# design.net
KiCad netlist of a schematic drawn in EasyEDA Pro
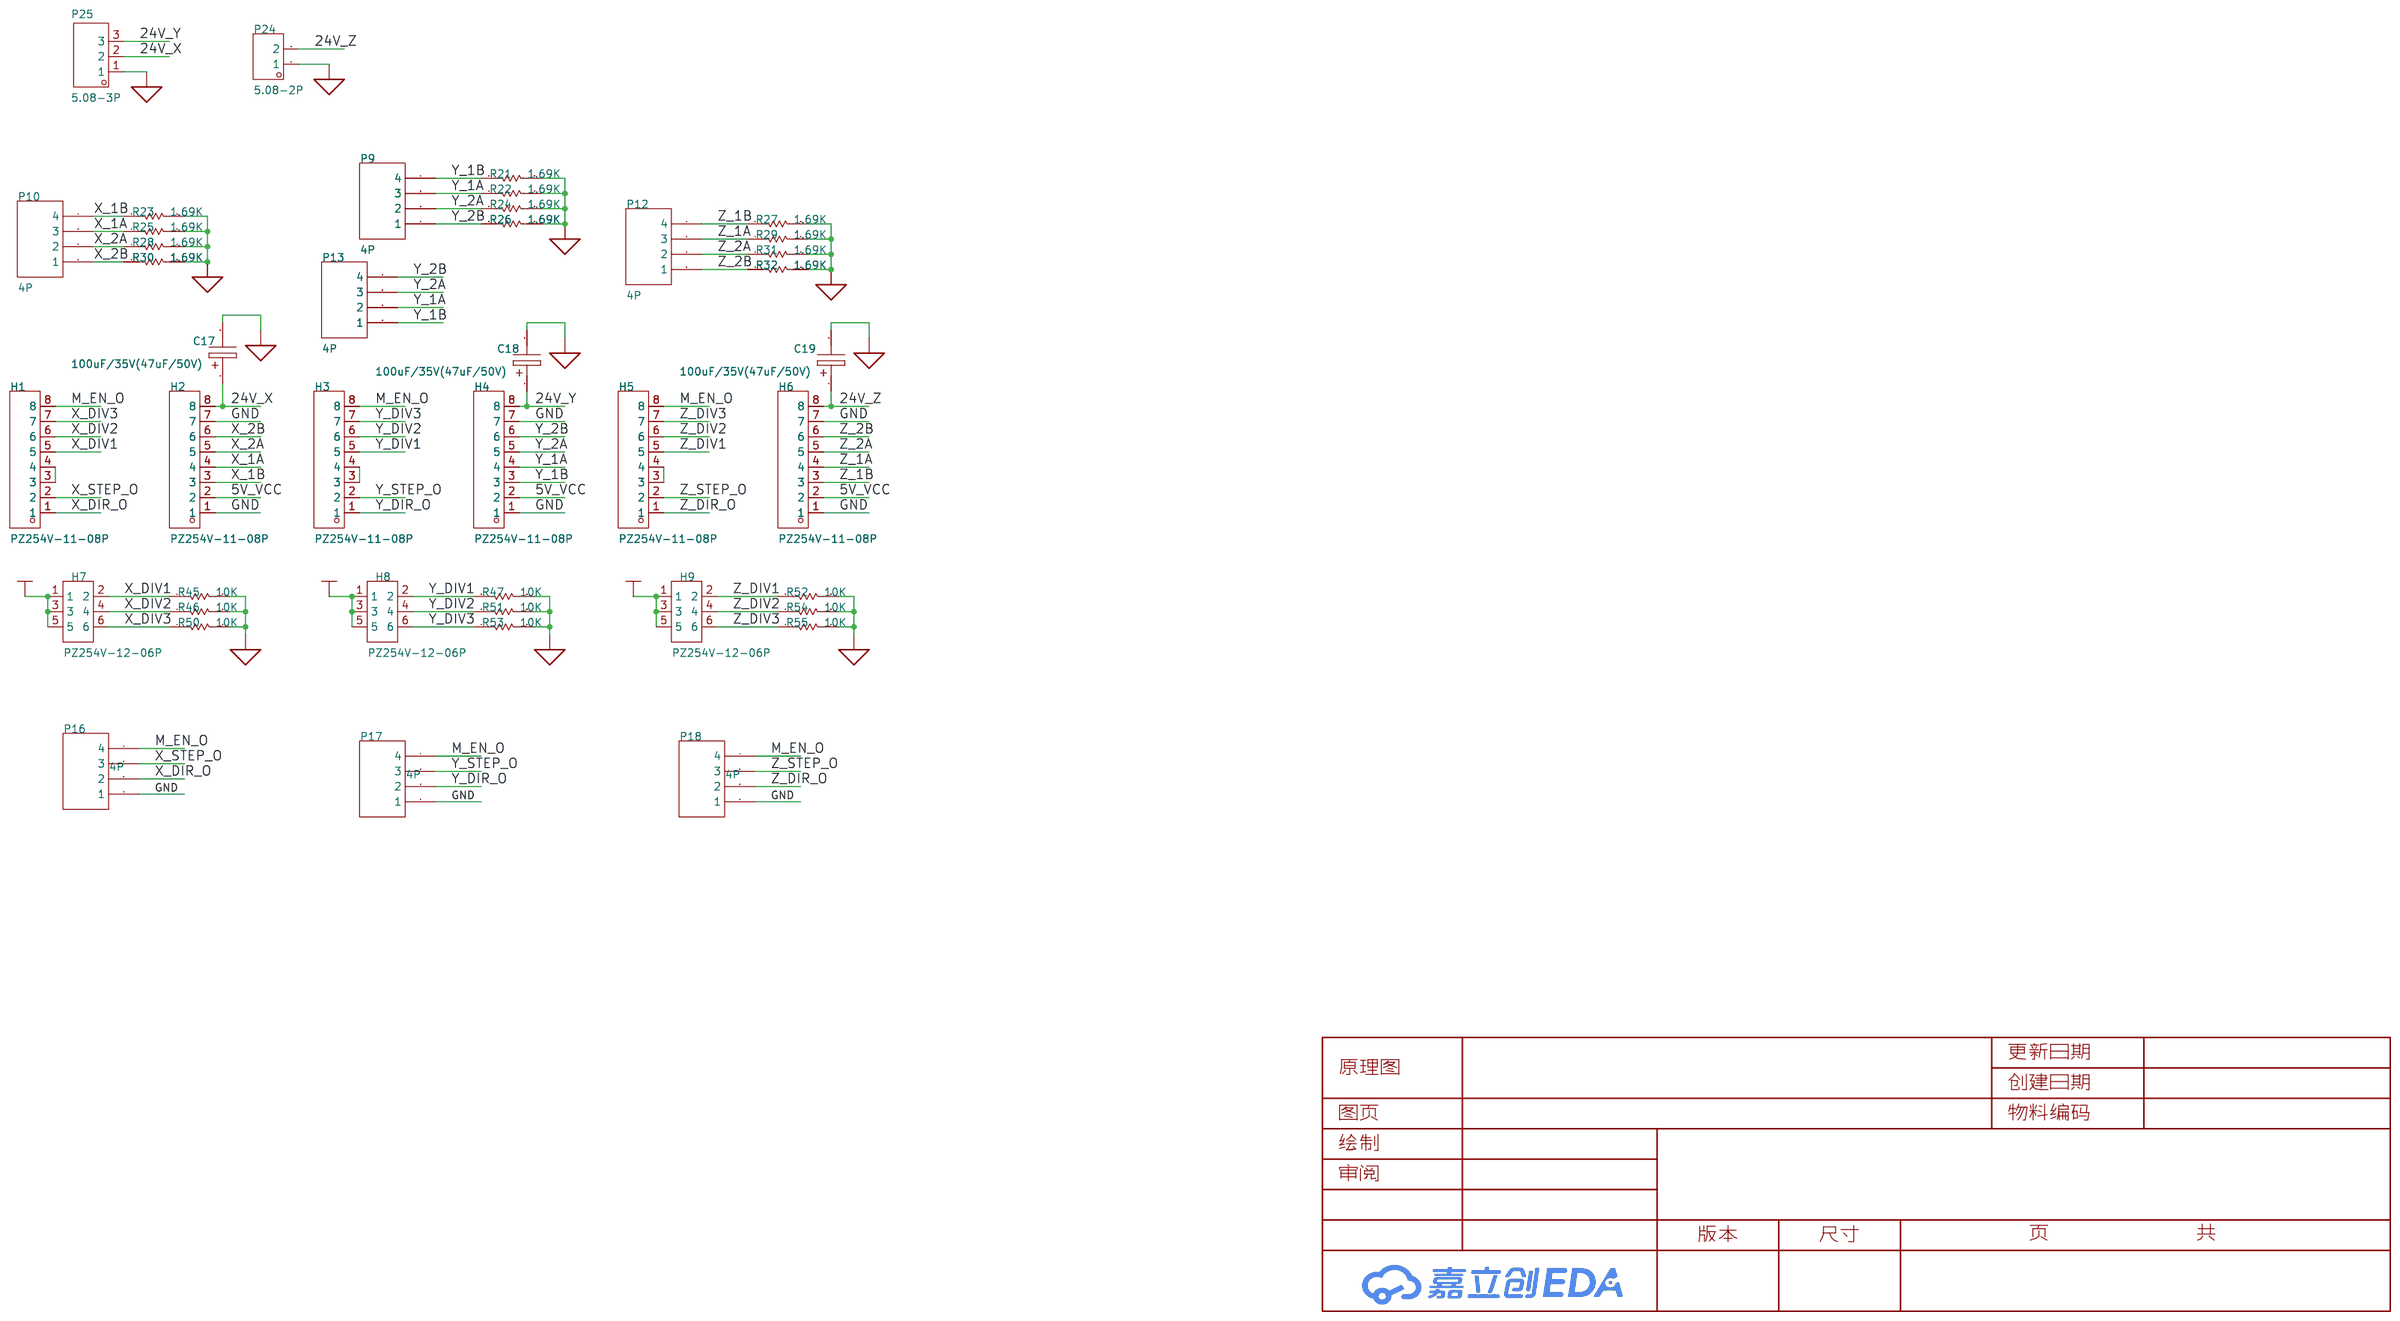
[diagram p0: schematic sheet]

(export (version "E")
  (design (tool "Eeschema 10.0.6"))
  (components
    (comp (ref "C17")
      (value "100uF/35V(47uF/50V)")
      (footprint "easyedapro:电解电容贴片10x10")
      (libsource (lib "easyedapro") (part "ELECTRO1"))
    )
    (comp (ref "C18")
      (value "100uF/35V(47uF/50V)")
      (footprint "easyedapro:电解电容贴片10x10")
      (libsource (lib "easyedapro") (part "ELECTRO1"))
    )
    (comp (ref "C19")
      (value "100uF/35V(47uF/50V)")
      (footprint "easyedapro:电解电容贴片10x10")
      (libsource (lib "easyedapro") (part "ELECTRO1"))
    )
    (comp (ref "H1")
      (value "PZ254V-11-08P")
      (footprint "easyedapro:HDR-TH_8P-P2.54-V-M")
      (fields (field (name "Manufacturer") "XFCN(兴飞)"))
      (libsource (lib "easyedapro") (part "PZ254V-11-08P"))
    )
    (comp (ref "H2")
      (value "PZ254V-11-08P")
      (footprint "easyedapro:HDR-TH_8P-P2.54-V-M")
      (fields (field (name "Manufacturer") "XFCN(兴飞)"))
      (libsource (lib "easyedapro") (part "PZ254V-11-08P"))
    )
    (comp (ref "H3")
      (value "PZ254V-11-08P")
      (footprint "easyedapro:HDR-TH_8P-P2.54-V-M")
      (fields (field (name "Manufacturer") "XFCN(兴飞)"))
      (libsource (lib "easyedapro") (part "PZ254V-11-08P"))
    )
    (comp (ref "H4")
      (value "PZ254V-11-08P")
      (footprint "easyedapro:HDR-TH_8P-P2.54-V-M")
      (fields (field (name "Manufacturer") "XFCN(兴飞)"))
      (libsource (lib "easyedapro") (part "PZ254V-11-08P"))
    )
    (comp (ref "H5")
      (value "PZ254V-11-08P")
      (footprint "easyedapro:HDR-TH_8P-P2.54-V-M")
      (fields (field (name "Manufacturer") "XFCN(兴飞)"))
      (libsource (lib "easyedapro") (part "PZ254V-11-08P"))
    )
    (comp (ref "H6")
      (value "PZ254V-11-08P")
      (footprint "easyedapro:HDR-TH_8P-P2.54-V-M")
      (fields (field (name "Manufacturer") "XFCN(兴飞)"))
      (libsource (lib "easyedapro") (part "PZ254V-11-08P"))
    )
    (comp (ref "H7")
      (value "PZ254V-12-06P")
      (footprint "easyedapro:HDR-TH_PZ254V-12-06P-A40")
      (description "排针2.54mm间距 直插 2x03位 直针外露4mm")
      (fields (field (name "Manufacturer") "XFCN(兴飞)"))
      (libsource (lib "easyedapro") (part "PZ254V-12-06P-A40"))
    )
    (comp (ref "H8")
      (value "PZ254V-12-06P")
      (footprint "easyedapro:HDR-TH_PZ254V-12-06P-A40")
      (description "排针2.54mm间距 直插 2x03位 直针外露4mm")
      (fields (field (name "Manufacturer") "XFCN(兴飞)"))
      (libsource (lib "easyedapro") (part "PZ254V-12-06P-A40"))
    )
    (comp (ref "H9")
      (value "PZ254V-12-06P")
      (footprint "easyedapro:HDR-TH_PZ254V-12-06P-A40")
      (description "排针2.54mm间距 直插 2x03位 直针外露4mm")
      (fields (field (name "Manufacturer") "XFCN(兴飞)"))
      (libsource (lib "easyedapro") (part "PZ254V-12-06P-A40"))
    )
    (comp (ref "P9")
      (value "4P")
      (footprint "easyedapro:HDR1X4_CON")
      (libsource (lib "easyedapro") (part "4P"))
    )
    (comp (ref "P10")
      (value "4P")
      (footprint "easyedapro:HDR1X4_CON")
      (libsource (lib "easyedapro") (part "4P"))
    )
    (comp (ref "P12")
      (value "4P")
      (footprint "easyedapro:HDR1X4_CON")
      (libsource (lib "easyedapro") (part "4P"))
    )
    (comp (ref "P13")
      (value "4P")
      (footprint "easyedapro:HDR1X4_CON")
      (libsource (lib "easyedapro") (part "4P"))
    )
    (comp (ref "P16") (value "4P") (libsource (lib "") (part "4P_1")))
    (comp (ref "P17") (value "4P") (libsource (lib "") (part "4P_1")))
    (comp (ref "P18") (value "4P") (libsource (lib "") (part "4P_1")))
    (comp (ref "P24")
      (value "5.08-2P")
      (footprint "easyedapro:CONN-TH_WJ2EDGVC-5.08-2P")
      (fields (field (name "Manufacturer") "KANGNEX(康奈克斯电气)"))
      (libsource (lib "easyedapro") (part "WJ2EDGVC-5.08-2P"))
    )
    (comp (ref "P25")
      (value "5.08-3P")
      (footprint "easyedapro:CONN-TH_3P-P5.08-WJ2EDGVC-3P")
      (description "连接器类型:板端/插座-闭口;间距:5.08mm;排数:1;每排PIN数:3;安装方式:直针;颜色:绿色;")
      (fields (field (name "Manufacturer") "KANGNEX(康奈克斯电气)"))
      (libsource (lib "easyedapro") (part "WJ2EDGVC-3P"))
    )
    (comp (ref "R21")
      (value "10K")
      (footprint "easyedapro:0603R")
      (description "Resistor")
      (libsource (lib "easyedapro") (part "10K"))
    )
    (comp (ref "R22")
      (value "10K")
      (footprint "easyedapro:0603R")
      (description "Resistor")
      (libsource (lib "easyedapro") (part "10K"))
    )
    (comp (ref "R23")
      (value "10K")
      (footprint "easyedapro:0603R")
      (description "Resistor")
      (libsource (lib "easyedapro") (part "10K"))
    )
    (comp (ref "R24")
      (value "10K")
      (footprint "easyedapro:0603R")
      (description "Resistor")
      (libsource (lib "easyedapro") (part "10K"))
    )
    (comp (ref "R25")
      (value "10K")
      (footprint "easyedapro:0603R")
      (description "Resistor")
      (libsource (lib "easyedapro") (part "10K"))
    )
    (comp (ref "R26")
      (value "10K")
      (footprint "easyedapro:0603R")
      (description "Resistor")
      (libsource (lib "easyedapro") (part "10K"))
    )
    (comp (ref "R27")
      (value "10K")
      (footprint "easyedapro:0603R")
      (description "Resistor")
      (libsource (lib "easyedapro") (part "10K"))
    )
    (comp (ref "R28")
      (value "10K")
      (footprint "easyedapro:0603R")
      (description "Resistor")
      (libsource (lib "easyedapro") (part "10K"))
    )
    (comp (ref "R29")
      (value "10K")
      (footprint "easyedapro:0603R")
      (description "Resistor")
      (libsource (lib "easyedapro") (part "10K"))
    )
    (comp (ref "R30")
      (value "10K")
      (footprint "easyedapro:0603R")
      (description "Resistor")
      (libsource (lib "easyedapro") (part "10K"))
    )
    (comp (ref "R31")
      (value "10K")
      (footprint "easyedapro:0603R")
      (description "Resistor")
      (libsource (lib "easyedapro") (part "10K"))
    )
    (comp (ref "R32")
      (value "10K")
      (footprint "easyedapro:0603R")
      (description "Resistor")
      (libsource (lib "easyedapro") (part "10K"))
    )
    (comp (ref "R45")
      (value "10K")
      (footprint "easyedapro:0603R")
      (description "Resistor")
      (libsource (lib "easyedapro") (part "10K"))
    )
    (comp (ref "R46")
      (value "10K")
      (footprint "easyedapro:0603R")
      (description "Resistor")
      (libsource (lib "easyedapro") (part "10K"))
    )
    (comp (ref "R47")
      (value "10K")
      (footprint "easyedapro:0603R")
      (description "Resistor")
      (libsource (lib "easyedapro") (part "10K"))
    )
    (comp (ref "R50")
      (value "10K")
      (footprint "easyedapro:0603R")
      (description "Resistor")
      (libsource (lib "easyedapro") (part "10K"))
    )
    (comp (ref "R51")
      (value "10K")
      (footprint "easyedapro:0603R")
      (description "Resistor")
      (libsource (lib "easyedapro") (part "10K"))
    )
    (comp (ref "R52")
      (value "10K")
      (footprint "easyedapro:0603R")
      (description "Resistor")
      (libsource (lib "easyedapro") (part "10K"))
    )
    (comp (ref "R53")
      (value "10K")
      (footprint "easyedapro:0603R")
      (description "Resistor")
      (libsource (lib "easyedapro") (part "10K"))
    )
    (comp (ref "R54")
      (value "10K")
      (footprint "easyedapro:0603R")
      (description "Resistor")
      (libsource (lib "easyedapro") (part "10K"))
    )
    (comp (ref "R55")
      (value "10K")
      (footprint "easyedapro:0603R")
      (description "Resistor")
      (libsource (lib "easyedapro") (part "10K"))
    )
  )
  (nets
    (net (code "1") (name "/24V_X") (class "Default")
      (node (ref "C17") (pin "1") (pintype "unspecified"))
      (node (ref "H2") (pin "8") (pinfunction "8_8") (pintype "unspecified"))
      (node (ref "P25") (pin "2") (pinfunction "2_2") (pintype "input"))
    )
    (net (code "2") (name "/24V_Y") (class "Default")
      (node (ref "C18") (pin "1") (pintype "unspecified"))
      (node (ref "H4") (pin "8") (pinfunction "8_8") (pintype "unspecified"))
      (node (ref "P25") (pin "3") (pinfunction "3_3") (pintype "input"))
    )
    (net (code "3") (name "/24V_Z") (class "Default")
      (node (ref "C19") (pin "1") (pintype "unspecified"))
      (node (ref "H6") (pin "8") (pinfunction "8_8") (pintype "unspecified"))
      (node (ref "P24") (pin "2") (pinfunction "2_2") (pintype "unspecified"))
    )
    (net (code "4") (name "/M_EN_O") (class "Default")
      (node (ref "H1") (pin "8") (pinfunction "8_8") (pintype "unspecified"))
      (node (ref "H3") (pin "8") (pinfunction "8_8") (pintype "unspecified"))
      (node (ref "H5") (pin "8") (pinfunction "8_8") (pintype "unspecified"))
      (node (ref "P16") (pin "4") (pinfunction "4_4") (pintype "input"))
      (node (ref "P17") (pin "4") (pinfunction "4_4") (pintype "input"))
      (node (ref "P18") (pin "4") (pinfunction "4_4") (pintype "input"))
    )
    (net (code "5") (name "/X_1A") (class "Default")
      (node (ref "H2") (pin "4") (pinfunction "4_4") (pintype "unspecified"))
      (node (ref "P10") (pin "3") (pinfunction "3_3") (pintype "unspecified"))
      (node (ref "R25") (pin "1") (pinfunction "1_1") (pintype "unspecified"))
    )
    (net (code "6") (name "/X_1B") (class "Default")
      (node (ref "H2") (pin "3") (pinfunction "3_3") (pintype "unspecified"))
      (node (ref "P10") (pin "4") (pinfunction "4_4") (pintype "unspecified"))
      (node (ref "R23") (pin "1") (pinfunction "1_1") (pintype "unspecified"))
    )
    (net (code "7") (name "/X_2A") (class "Default")
      (node (ref "H2") (pin "5") (pinfunction "5_5") (pintype "unspecified"))
      (node (ref "P10") (pin "2") (pinfunction "2_2") (pintype "unspecified"))
      (node (ref "R28") (pin "1") (pinfunction "1_1") (pintype "unspecified"))
    )
    (net (code "8") (name "/X_2B") (class "Default")
      (node (ref "H2") (pin "6") (pinfunction "6_6") (pintype "unspecified"))
      (node (ref "P10") (pin "1") (pinfunction "1_1") (pintype "unspecified"))
      (node (ref "R30") (pin "1") (pinfunction "1_1") (pintype "unspecified"))
    )
    (net (code "9") (name "/X_DIR_O") (class "Default")
      (node (ref "H1") (pin "1") (pinfunction "1_1") (pintype "unspecified"))
      (node (ref "P16") (pin "2") (pinfunction "2_2") (pintype "input"))
    )
    (net (code "10") (name "/X_DIV1") (class "Default")
      (node (ref "H1") (pin "5") (pinfunction "5_5") (pintype "unspecified"))
      (node (ref "H7") (pin "2") (pinfunction "2_2") (pintype "unspecified"))
      (node (ref "R45") (pin "1") (pinfunction "1_1") (pintype "unspecified"))
    )
    (net (code "11") (name "/X_DIV2") (class "Default")
      (node (ref "H1") (pin "6") (pinfunction "6_6") (pintype "unspecified"))
      (node (ref "H7") (pin "4") (pinfunction "4_4") (pintype "unspecified"))
      (node (ref "R46") (pin "1") (pinfunction "1_1") (pintype "unspecified"))
    )
    (net (code "12") (name "/X_DIV3") (class "Default")
      (node (ref "H1") (pin "7") (pinfunction "7_7") (pintype "unspecified"))
      (node (ref "H7") (pin "6") (pinfunction "6_6") (pintype "unspecified"))
      (node (ref "R50") (pin "1") (pinfunction "1_1") (pintype "unspecified"))
    )
    (net (code "13") (name "/X_STEP_O") (class "Default")
      (node (ref "H1") (pin "2") (pinfunction "2_2") (pintype "unspecified"))
      (node (ref "P16") (pin "3") (pinfunction "3_3") (pintype "input"))
    )
    (net (code "14") (name "/Y_1A") (class "Default")
      (node (ref "H4") (pin "4") (pinfunction "4_4") (pintype "unspecified"))
      (node (ref "P13") (pin "2") (pinfunction "2_2") (pintype "unspecified"))
      (node (ref "P9") (pin "3") (pinfunction "3_3") (pintype "unspecified"))
      (node (ref "R22") (pin "1") (pinfunction "1_1") (pintype "unspecified"))
    )
    (net (code "15") (name "/Y_1B") (class "Default")
      (node (ref "H4") (pin "3") (pinfunction "3_3") (pintype "unspecified"))
      (node (ref "P13") (pin "1") (pinfunction "1_1") (pintype "unspecified"))
      (node (ref "P9") (pin "4") (pinfunction "4_4") (pintype "unspecified"))
      (node (ref "R21") (pin "1") (pinfunction "1_1") (pintype "unspecified"))
    )
    (net (code "16") (name "/Y_2A") (class "Default")
      (node (ref "H4") (pin "5") (pinfunction "5_5") (pintype "unspecified"))
      (node (ref "P13") (pin "3") (pinfunction "3_3") (pintype "unspecified"))
      (node (ref "P9") (pin "2") (pinfunction "2_2") (pintype "unspecified"))
      (node (ref "R24") (pin "1") (pinfunction "1_1") (pintype "unspecified"))
    )
    (net (code "17") (name "/Y_2B") (class "Default")
      (node (ref "H4") (pin "6") (pinfunction "6_6") (pintype "unspecified"))
      (node (ref "P13") (pin "4") (pinfunction "4_4") (pintype "unspecified"))
      (node (ref "P9") (pin "1") (pinfunction "1_1") (pintype "unspecified"))
      (node (ref "R26") (pin "1") (pinfunction "1_1") (pintype "unspecified"))
    )
    (net (code "18") (name "/Y_DIR_O") (class "Default")
      (node (ref "H3") (pin "1") (pinfunction "1_1") (pintype "unspecified"))
      (node (ref "P17") (pin "2") (pinfunction "2_2") (pintype "input"))
    )
    (net (code "19") (name "/Y_DIV1") (class "Default")
      (node (ref "H3") (pin "5") (pinfunction "5_5") (pintype "unspecified"))
      (node (ref "H8") (pin "2") (pinfunction "2_2") (pintype "unspecified"))
      (node (ref "R47") (pin "1") (pinfunction "1_1") (pintype "unspecified"))
    )
    (net (code "20") (name "/Y_DIV2") (class "Default")
      (node (ref "H3") (pin "6") (pinfunction "6_6") (pintype "unspecified"))
      (node (ref "H8") (pin "4") (pinfunction "4_4") (pintype "unspecified"))
      (node (ref "R51") (pin "1") (pinfunction "1_1") (pintype "unspecified"))
    )
    (net (code "21") (name "/Y_DIV3") (class "Default")
      (node (ref "H3") (pin "7") (pinfunction "7_7") (pintype "unspecified"))
      (node (ref "H8") (pin "6") (pinfunction "6_6") (pintype "unspecified"))
      (node (ref "R53") (pin "1") (pinfunction "1_1") (pintype "unspecified"))
    )
    (net (code "22") (name "/Y_STEP_O") (class "Default")
      (node (ref "H3") (pin "2") (pinfunction "2_2") (pintype "unspecified"))
      (node (ref "P17") (pin "3") (pinfunction "3_3") (pintype "input"))
    )
    (net (code "23") (name "/Z_1A") (class "Default")
      (node (ref "H6") (pin "4") (pinfunction "4_4") (pintype "unspecified"))
      (node (ref "P12") (pin "3") (pinfunction "3_3") (pintype "unspecified"))
      (node (ref "R29") (pin "1") (pinfunction "1_1") (pintype "unspecified"))
    )
    (net (code "24") (name "/Z_1B") (class "Default")
      (node (ref "H6") (pin "3") (pinfunction "3_3") (pintype "unspecified"))
      (node (ref "P12") (pin "4") (pinfunction "4_4") (pintype "unspecified"))
      (node (ref "R27") (pin "1") (pinfunction "1_1") (pintype "unspecified"))
    )
    (net (code "25") (name "/Z_2A") (class "Default")
      (node (ref "H6") (pin "5") (pinfunction "5_5") (pintype "unspecified"))
      (node (ref "P12") (pin "2") (pinfunction "2_2") (pintype "unspecified"))
      (node (ref "R31") (pin "1") (pinfunction "1_1") (pintype "unspecified"))
    )
    (net (code "26") (name "/Z_2B") (class "Default")
      (node (ref "H6") (pin "6") (pinfunction "6_6") (pintype "unspecified"))
      (node (ref "P12") (pin "1") (pinfunction "1_1") (pintype "unspecified"))
      (node (ref "R32") (pin "1") (pinfunction "1_1") (pintype "unspecified"))
    )
    (net (code "27") (name "/Z_DIR_O") (class "Default")
      (node (ref "H5") (pin "1") (pinfunction "1_1") (pintype "unspecified"))
      (node (ref "P18") (pin "2") (pinfunction "2_2") (pintype "input"))
    )
    (net (code "28") (name "/Z_DIV1") (class "Default")
      (node (ref "H5") (pin "5") (pinfunction "5_5") (pintype "unspecified"))
      (node (ref "H9") (pin "2") (pinfunction "2_2") (pintype "unspecified"))
      (node (ref "R52") (pin "1") (pinfunction "1_1") (pintype "unspecified"))
    )
    (net (code "29") (name "/Z_DIV2") (class "Default")
      (node (ref "H5") (pin "6") (pinfunction "6_6") (pintype "unspecified"))
      (node (ref "H9") (pin "4") (pinfunction "4_4") (pintype "unspecified"))
      (node (ref "R54") (pin "1") (pinfunction "1_1") (pintype "unspecified"))
    )
    (net (code "30") (name "/Z_DIV3") (class "Default")
      (node (ref "H5") (pin "7") (pinfunction "7_7") (pintype "unspecified"))
      (node (ref "H9") (pin "6") (pinfunction "6_6") (pintype "unspecified"))
      (node (ref "R55") (pin "1") (pinfunction "1_1") (pintype "unspecified"))
    )
    (net (code "31") (name "/Z_STEP_O") (class "Default")
      (node (ref "H5") (pin "2") (pinfunction "2_2") (pintype "unspecified"))
      (node (ref "P18") (pin "3") (pinfunction "3_3") (pintype "input"))
    )
    (net (code "32") (name "5V_VCC") (class "Default")
      (node (ref "H2") (pin "2") (pinfunction "2_2") (pintype "unspecified"))
      (node (ref "H4") (pin "2") (pinfunction "2_2") (pintype "unspecified"))
      (node (ref "H6") (pin "2") (pinfunction "2_2") (pintype "unspecified"))
      (node (ref "H7") (pin "1") (pinfunction "1_1") (pintype "unspecified"))
      (node (ref "H7") (pin "3") (pinfunction "3_3") (pintype "unspecified"))
      (node (ref "H7") (pin "5") (pinfunction "5_5") (pintype "unspecified"))
      (node (ref "H8") (pin "1") (pinfunction "1_1") (pintype "unspecified"))
      (node (ref "H8") (pin "3") (pinfunction "3_3") (pintype "unspecified"))
      (node (ref "H8") (pin "5") (pinfunction "5_5") (pintype "unspecified"))
      (node (ref "H9") (pin "1") (pinfunction "1_1") (pintype "unspecified"))
      (node (ref "H9") (pin "3") (pinfunction "3_3") (pintype "unspecified"))
      (node (ref "H9") (pin "5") (pinfunction "5_5") (pintype "unspecified"))
    )
    (net (code "33") (name "GND") (class "Default")
      (node (ref "C17") (pin "2") (pintype "unspecified"))
      (node (ref "C18") (pin "2") (pintype "unspecified"))
      (node (ref "C19") (pin "2") (pintype "unspecified"))
      (node (ref "H2") (pin "1") (pinfunction "1_1") (pintype "unspecified"))
      (node (ref "H2") (pin "7") (pinfunction "7_7") (pintype "unspecified"))
      (node (ref "H4") (pin "1") (pinfunction "1_1") (pintype "unspecified"))
      (node (ref "H4") (pin "7") (pinfunction "7_7") (pintype "unspecified"))
      (node (ref "H6") (pin "1") (pinfunction "1_1") (pintype "unspecified"))
      (node (ref "H6") (pin "7") (pinfunction "7_7") (pintype "unspecified"))
      (node (ref "P16") (pin "1") (pinfunction "1_1") (pintype "input"))
      (node (ref "P17") (pin "1") (pinfunction "1_1") (pintype "input"))
      (node (ref "P18") (pin "1") (pinfunction "1_1") (pintype "input"))
      (node (ref "P24") (pin "1") (pinfunction "1_1") (pintype "unspecified"))
      (node (ref "P25") (pin "1") (pinfunction "1_1") (pintype "input"))
      (node (ref "R21") (pin "2") (pinfunction "2_2") (pintype "unspecified"))
      (node (ref "R22") (pin "2") (pinfunction "2_2") (pintype "unspecified"))
      (node (ref "R23") (pin "2") (pinfunction "2_2") (pintype "unspecified"))
      (node (ref "R24") (pin "2") (pinfunction "2_2") (pintype "unspecified"))
      (node (ref "R25") (pin "2") (pinfunction "2_2") (pintype "unspecified"))
      (node (ref "R26") (pin "2") (pinfunction "2_2") (pintype "unspecified"))
      (node (ref "R27") (pin "2") (pinfunction "2_2") (pintype "unspecified"))
      (node (ref "R28") (pin "2") (pinfunction "2_2") (pintype "unspecified"))
      (node (ref "R29") (pin "2") (pinfunction "2_2") (pintype "unspecified"))
      (node (ref "R30") (pin "2") (pinfunction "2_2") (pintype "unspecified"))
      (node (ref "R31") (pin "2") (pinfunction "2_2") (pintype "unspecified"))
      (node (ref "R32") (pin "2") (pinfunction "2_2") (pintype "unspecified"))
      (node (ref "R45") (pin "2") (pinfunction "2_2") (pintype "unspecified"))
      (node (ref "R46") (pin "2") (pinfunction "2_2") (pintype "unspecified"))
      (node (ref "R47") (pin "2") (pinfunction "2_2") (pintype "unspecified"))
      (node (ref "R50") (pin "2") (pinfunction "2_2") (pintype "unspecified"))
      (node (ref "R51") (pin "2") (pinfunction "2_2") (pintype "unspecified"))
      (node (ref "R52") (pin "2") (pinfunction "2_2") (pintype "unspecified"))
      (node (ref "R53") (pin "2") (pinfunction "2_2") (pintype "unspecified"))
      (node (ref "R54") (pin "2") (pinfunction "2_2") (pintype "unspecified"))
      (node (ref "R55") (pin "2") (pinfunction "2_2") (pintype "unspecified"))
    )
    (net (code "34") (name "Net-(H1-Pad3)") (class "Default")
      (node (ref "H1") (pin "3") (pinfunction "3_3") (pintype "unspecified"))
      (node (ref "H1") (pin "4") (pinfunction "4_4") (pintype "unspecified"))
    )
    (net (code "35") (name "Net-(H3-Pad3)") (class "Default")
      (node (ref "H3") (pin "3") (pinfunction "3_3") (pintype "unspecified"))
      (node (ref "H3") (pin "4") (pinfunction "4_4") (pintype "unspecified"))
    )
    (net (code "36") (name "Net-(H5-Pad3)") (class "Default")
      (node (ref "H5") (pin "3") (pinfunction "3_3") (pintype "unspecified"))
      (node (ref "H5") (pin "4") (pinfunction "4_4") (pintype "unspecified"))
    )
  )
)
